# axiom_beta_plugin_module_1xHDMI_v0_4_e11.net
KiCad netlist of a schematic drawn in EAGLE
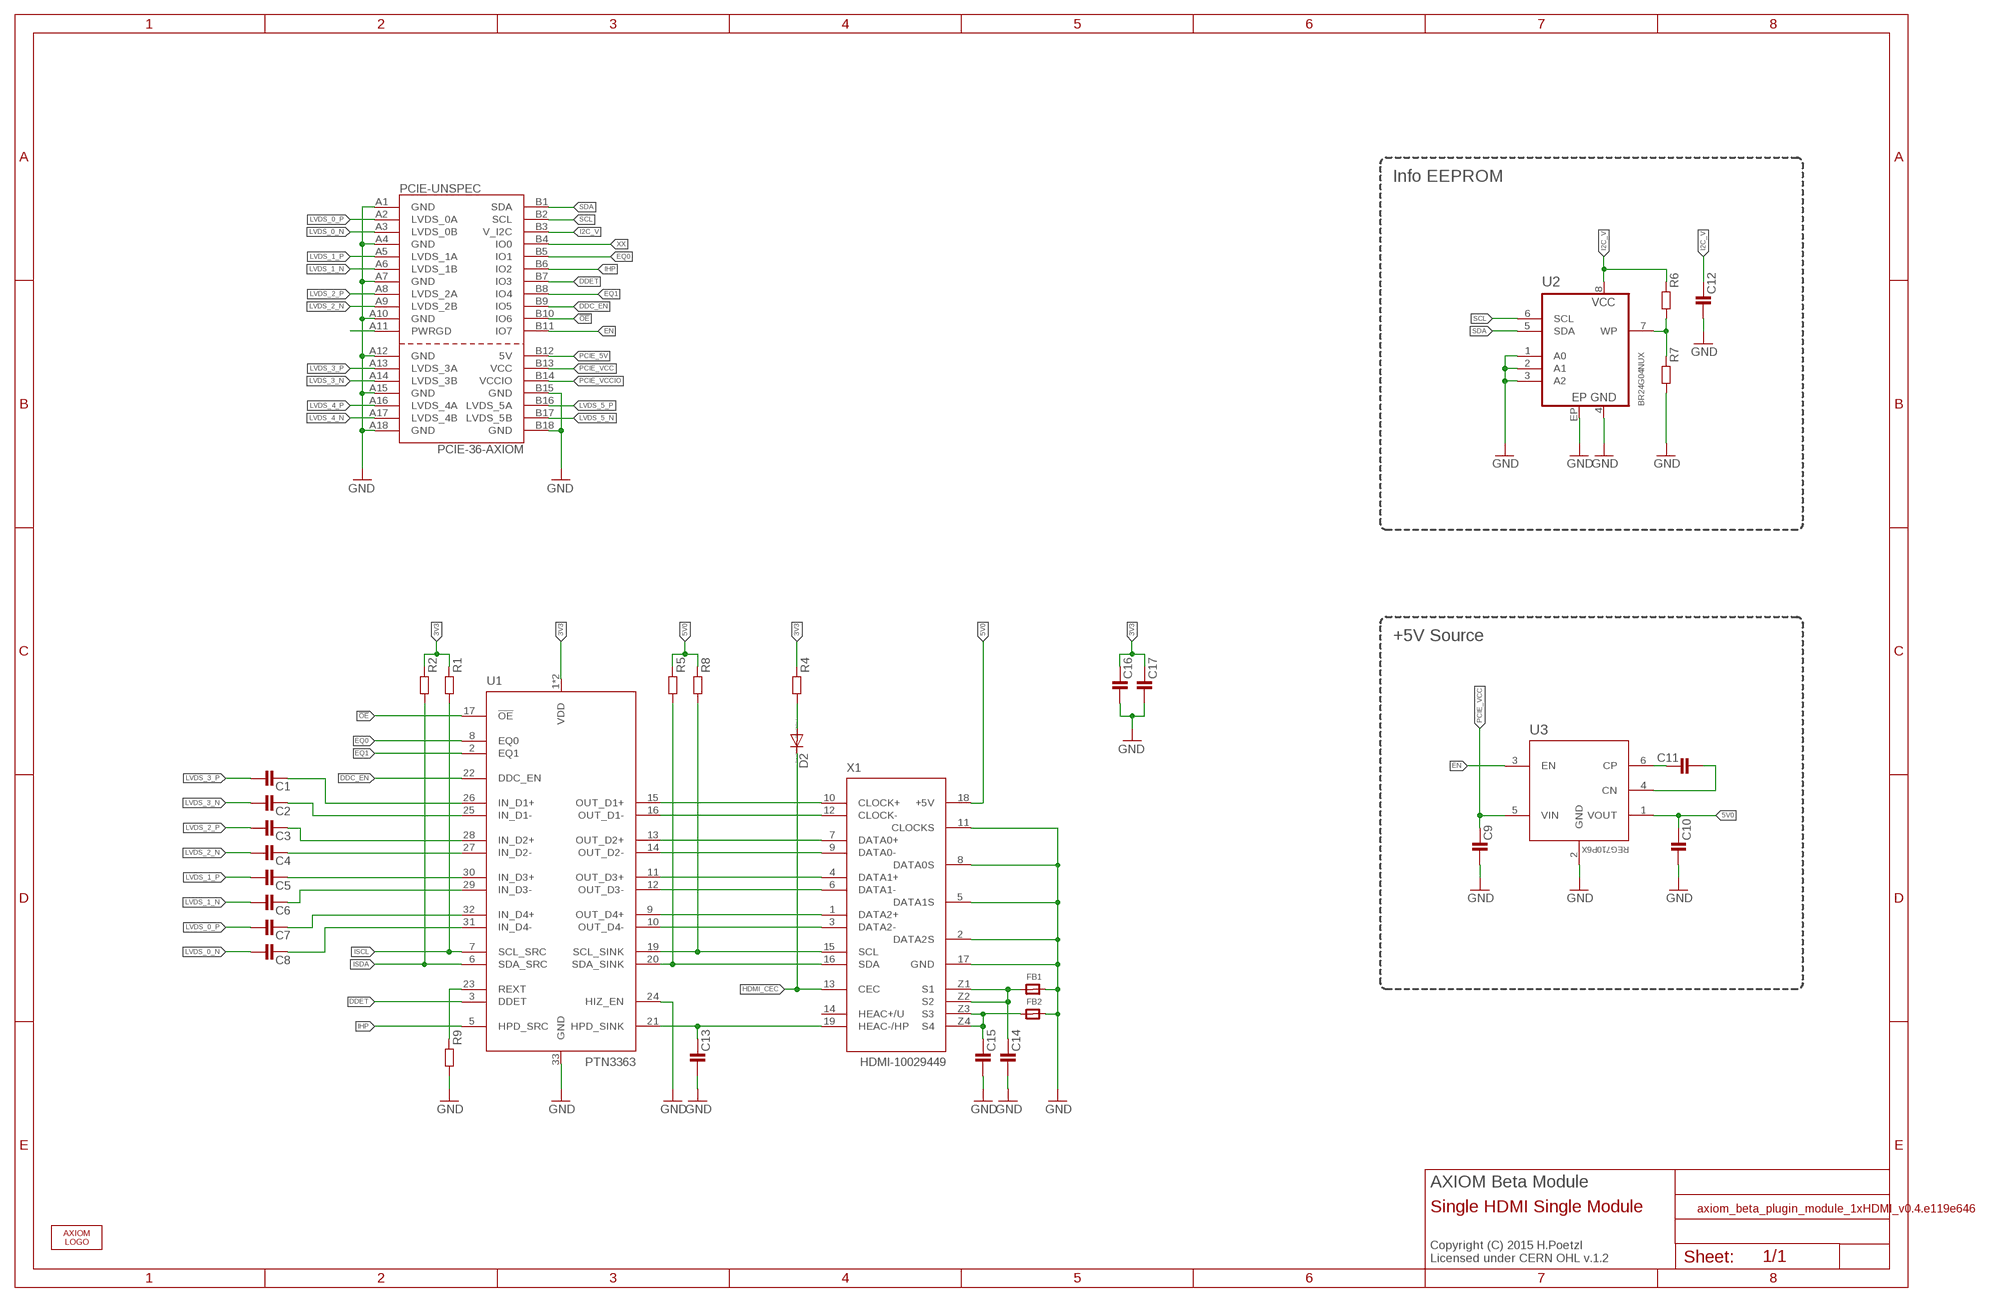
[diagram p0: schematic, sheet 1]

(export (version "E")
  (design (tool "Eeschema 10.0.6"))
  (components
    (comp (ref "C1")
      (value "C0402-B")
      (footprint "eagle-import:0402-B")
      (libsource (lib "eagle-import") (part "C0402-B"))
    )
    (comp (ref "C2")
      (value "C0402-B")
      (footprint "eagle-import:0402-B")
      (libsource (lib "eagle-import") (part "C0402-B"))
    )
    (comp (ref "C3")
      (value "C0402-B")
      (footprint "eagle-import:0402-B")
      (libsource (lib "eagle-import") (part "C0402-B"))
    )
    (comp (ref "C4")
      (value "C0402-B")
      (footprint "eagle-import:0402-B")
      (libsource (lib "eagle-import") (part "C0402-B"))
    )
    (comp (ref "C5")
      (value "C0402-B")
      (footprint "eagle-import:0402-B")
      (libsource (lib "eagle-import") (part "C0402-B"))
    )
    (comp (ref "C6")
      (value "C0402-B")
      (footprint "eagle-import:0402-B")
      (libsource (lib "eagle-import") (part "C0402-B"))
    )
    (comp (ref "C7")
      (value "C0402-B")
      (footprint "eagle-import:0402-B")
      (libsource (lib "eagle-import") (part "C0402-B"))
    )
    (comp (ref "C8")
      (value "C0402-B")
      (footprint "eagle-import:0402-B")
      (libsource (lib "eagle-import") (part "C0402-B"))
    )
    (comp (ref "C9")
      (value "C0603-B")
      (footprint "eagle-import:0603-B")
      (libsource (lib "eagle-import") (part "C0603-B"))
    )
    (comp (ref "C10")
      (value "C0603-B")
      (footprint "eagle-import:0603-B")
      (libsource (lib "eagle-import") (part "C0603-B"))
    )
    (comp (ref "C11")
      (value "C0603-B")
      (footprint "eagle-import:0603-B")
      (libsource (lib "eagle-import") (part "C0603-B"))
    )
    (comp (ref "C12")
      (value "C0402-B")
      (footprint "eagle-import:0402-B")
      (libsource (lib "eagle-import") (part "C0402-B"))
    )
    (comp (ref "C13")
      (value "C0402-B")
      (footprint "eagle-import:0402-B")
      (libsource (lib "eagle-import") (part "C0402-B"))
    )
    (comp (ref "C14")
      (value "C0402-B")
      (footprint "eagle-import:0402-B")
      (libsource (lib "eagle-import") (part "C0402-B"))
    )
    (comp (ref "C15")
      (value "C0402-B")
      (footprint "eagle-import:0402-B")
      (libsource (lib "eagle-import") (part "C0402-B"))
    )
    (comp (ref "C16")
      (value "C0402-B")
      (footprint "eagle-import:0402-B")
      (libsource (lib "eagle-import") (part "C0402-B"))
    )
    (comp (ref "C17")
      (value "C0402-B")
      (footprint "eagle-import:0402-B")
      (libsource (lib "eagle-import") (part "C0402-B"))
    )
    (comp (ref "D2")
      (value "DIODE-SOD523")
      (footprint "eagle-import:SOD523")
      (libsource (lib "eagle-import") (part "DIODE-SOD523"))
    )
    (comp (ref "FB1")
      (value "FERRITE_0603MP")
      (footprint "eagle-import:_0603MP")
      (libsource (lib "eagle-import") (part "FERRITE_0603MP"))
    )
    (comp (ref "FB2")
      (value "FERRITE_0603MP")
      (footprint "eagle-import:_0603MP")
      (libsource (lib "eagle-import") (part "FERRITE_0603MP"))
    )
    (comp (ref "PCIE-UNSPEC")
      (value "PCIE-36-AXIOM")
      (footprint "eagle-import:PCIE-36-AXIOM")
      (libsource (lib "eagle-import") (part "PCIE-36-AXIOM"))
    )
    (comp (ref "R1")
      (value "R0402-B")
      (footprint "eagle-import:0402-B")
      (libsource (lib "eagle-import") (part "R0402-B"))
    )
    (comp (ref "R2")
      (value "R0402-B")
      (footprint "eagle-import:0402-B")
      (libsource (lib "eagle-import") (part "R0402-B"))
    )
    (comp (ref "R4")
      (value "R0402-B")
      (footprint "eagle-import:0402-B")
      (libsource (lib "eagle-import") (part "R0402-B"))
    )
    (comp (ref "R5")
      (value "R0402-B")
      (footprint "eagle-import:0402-B")
      (libsource (lib "eagle-import") (part "R0402-B"))
    )
    (comp (ref "R6")
      (value "R0402-B")
      (footprint "eagle-import:0402-B")
      (libsource (lib "eagle-import") (part "R0402-B"))
    )
    (comp (ref "R7")
      (value "R0402-B")
      (footprint "eagle-import:0402-B")
      (libsource (lib "eagle-import") (part "R0402-B"))
    )
    (comp (ref "R8")
      (value "R0402-B")
      (footprint "eagle-import:0402-B")
      (libsource (lib "eagle-import") (part "R0402-B"))
    )
    (comp (ref "R9")
      (value "R0402-B")
      (footprint "eagle-import:0402-B")
      (libsource (lib "eagle-import") (part "R0402-B"))
    )
    (comp (ref "U$1")
      (value "AXIOM_LOGO459X70")
      (footprint "eagle-import:AXIOM_LOGO_459X70")
      (libsource (lib "eagle-import") (part "AXIOM_LOGO459X70"))
    )
    (comp (ref "U1")
      (value "PTN3363")
      (footprint "eagle-import:HVQFN32")
      (libsource (lib "eagle-import") (part "PTN3363"))
    )
    (comp (ref "U2")
      (value "BR24G04NUX")
      (footprint "eagle-import:DFN200X300X100-9N")
      (libsource (lib "eagle-import") (part "BR24G04NUX"))
    )
    (comp (ref "U3")
      (value "REG710P6X")
      (footprint "eagle-import:SOT65P210X110-6N")
      (libsource (lib "eagle-import") (part "REG710P6X"))
    )
    (comp (ref "X1")
      (value "HDMI-10029449")
      (footprint "eagle-import:10029449-X01XLF")
      (libsource (lib "eagle-import") (part "HDMI-10029449"))
    )
  )
  (nets
    (net (code "1") (name "/~{OE}") (class "Default")
      (node (ref "PCIE-UNSPEC") (pin "B10") (pinfunction "IO6_B10") (pintype "passive"))
      (node (ref "U1") (pin "17") (pinfunction "~{OE}_17") (pintype "bidirectional"))
    )
    (net (code "2") (name "3V3") (class "Default")
      (node (ref "C16") (pin "1") (pinfunction "1_1") (pintype "passive"))
      (node (ref "C17") (pin "1") (pinfunction "1_1") (pintype "passive"))
      (node (ref "R1") (pin "1") (pinfunction "1_1") (pintype "passive"))
      (node (ref "R2") (pin "1") (pinfunction "1_1") (pintype "passive"))
      (node (ref "R4") (pin "1") (pinfunction "1_1") (pintype "passive"))
      (node (ref "U1") (pin "1") (pinfunction "VDD_1") (pintype "power_in"))
      (node (ref "U1") (pin "18") (pinfunction "VDD_18") (pintype "power_in"))
    )
    (net (code "3") (name "5V0") (class "Default")
      (node (ref "C10") (pin "1") (pinfunction "1_1") (pintype "passive"))
      (node (ref "R5") (pin "1") (pinfunction "1_1") (pintype "passive"))
      (node (ref "R8") (pin "1") (pinfunction "1_1") (pintype "passive"))
      (node (ref "U3") (pin "1") (pinfunction "VOUT_1") (pintype "output"))
      (node (ref "X1") (pin "18") (pinfunction "+5V_18") (pintype "power_in"))
    )
    (net (code "4") (name "DDC_EN") (class "Default")
      (node (ref "PCIE-UNSPEC") (pin "B9") (pinfunction "IO5_B9") (pintype "passive"))
      (node (ref "U1") (pin "22") (pinfunction "DDC_EN_22") (pintype "bidirectional"))
    )
    (net (code "5") (name "DDET") (class "Default")
      (node (ref "PCIE-UNSPEC") (pin "B7") (pinfunction "IO3_B7") (pintype "passive"))
      (node (ref "U1") (pin "3") (pinfunction "DDET_3") (pintype "bidirectional"))
    )
    (net (code "6") (name "EN") (class "Default")
      (node (ref "PCIE-UNSPEC") (pin "B11") (pinfunction "IO7_B11") (pintype "passive"))
      (node (ref "U3") (pin "3") (pinfunction "EN_3") (pintype "input"))
    )
    (net (code "7") (name "EQ0") (class "Default")
      (node (ref "PCIE-UNSPEC") (pin "B5") (pinfunction "IO1_B5") (pintype "passive"))
      (node (ref "U1") (pin "8") (pinfunction "EQ0_8") (pintype "bidirectional"))
    )
    (net (code "8") (name "EQ1") (class "Default")
      (node (ref "PCIE-UNSPEC") (pin "B8") (pinfunction "IO4_B8") (pintype "passive"))
      (node (ref "U1") (pin "2") (pinfunction "EQ1_2") (pintype "bidirectional"))
    )
    (net (code "9") (name "GND") (class "Default")
      (node (ref "C10") (pin "2") (pinfunction "2_2") (pintype "passive"))
      (node (ref "C12") (pin "2") (pinfunction "2_2") (pintype "passive"))
      (node (ref "C13") (pin "2") (pinfunction "2_2") (pintype "passive"))
      (node (ref "C14") (pin "2") (pinfunction "2_2") (pintype "passive"))
      (node (ref "C15") (pin "2") (pinfunction "2_2") (pintype "passive"))
      (node (ref "C16") (pin "2") (pinfunction "2_2") (pintype "passive"))
      (node (ref "C17") (pin "2") (pinfunction "2_2") (pintype "passive"))
      (node (ref "C9") (pin "2") (pinfunction "2_2") (pintype "passive"))
      (node (ref "FB1") (pin "2") (pinfunction "P$2_2") (pintype "passive"))
      (node (ref "FB2") (pin "2") (pinfunction "P$2_2") (pintype "passive"))
      (node (ref "PCIE-UNSPEC") (pin "A1") (pinfunction "GND_A1") (pintype "passive"))
      (node (ref "PCIE-UNSPEC") (pin "A10") (pinfunction "GND_A10") (pintype "passive"))
      (node (ref "PCIE-UNSPEC") (pin "A12") (pinfunction "GND_A12") (pintype "passive"))
      (node (ref "PCIE-UNSPEC") (pin "A15") (pinfunction "GND_A15") (pintype "passive"))
      (node (ref "PCIE-UNSPEC") (pin "A18") (pinfunction "GND_A18") (pintype "passive"))
      (node (ref "PCIE-UNSPEC") (pin "A4") (pinfunction "GND_A4") (pintype "passive"))
      (node (ref "PCIE-UNSPEC") (pin "A7") (pinfunction "GND_A7") (pintype "passive"))
      (node (ref "PCIE-UNSPEC") (pin "B15") (pinfunction "GND_B15") (pintype "passive"))
      (node (ref "PCIE-UNSPEC") (pin "B18") (pinfunction "GND_B18") (pintype "passive"))
      (node (ref "R7") (pin "2") (pinfunction "2_2") (pintype "passive"))
      (node (ref "R9") (pin "2") (pinfunction "2_2") (pintype "passive"))
      (node (ref "U1") (pin "24") (pinfunction "HIZ_EN_24") (pintype "bidirectional"))
      (node (ref "U1") (pin "33") (pinfunction "GND_33") (pintype "bidirectional"))
      (node (ref "U2") (pin "1") (pinfunction "A0_1") (pintype "input"))
      (node (ref "U2") (pin "2") (pinfunction "A1_2") (pintype "input"))
      (node (ref "U2") (pin "3") (pinfunction "A2_3") (pintype "input"))
      (node (ref "U2") (pin "4") (pinfunction "GND_4") (pintype "passive"))
      (node (ref "U2") (pin "EP") (pinfunction "EP_EP") (pintype "passive"))
      (node (ref "U3") (pin "2") (pinfunction "GND_2") (pintype "passive"))
      (node (ref "X1") (pin "11") (pinfunction "CLOCKS_11") (pintype "power_in"))
      (node (ref "X1") (pin "17") (pinfunction "GND_17") (pintype "bidirectional"))
      (node (ref "X1") (pin "2") (pinfunction "DATA2S_2") (pintype "power_in"))
      (node (ref "X1") (pin "5") (pinfunction "DATA1S_5") (pintype "power_in"))
      (node (ref "X1") (pin "8") (pinfunction "DATA0S_8") (pintype "power_in"))
    )
    (net (code "10") (name "HDMI_CEC") (class "Default")
      (node (ref "D2") (pin "C") (pinfunction "C_C") (pintype "passive"))
      (node (ref "X1") (pin "13") (pinfunction "CEC_13") (pintype "bidirectional"))
    )
    (net (code "11") (name "I2C_V") (class "Default")
      (node (ref "C12") (pin "1") (pinfunction "1_1") (pintype "passive"))
      (node (ref "PCIE-UNSPEC") (pin "B3") (pinfunction "V_I2C_B3") (pintype "passive"))
      (node (ref "R6") (pin "1") (pinfunction "1_1") (pintype "passive"))
      (node (ref "U2") (pin "8") (pinfunction "VCC_8") (pintype "power_in"))
    )
    (net (code "12") (name "IHP") (class "Default")
      (node (ref "PCIE-UNSPEC") (pin "B6") (pinfunction "IO2_B6") (pintype "passive"))
      (node (ref "U1") (pin "5") (pinfunction "HPD_SRC_5") (pintype "bidirectional"))
    )
    (net (code "13") (name "ISCL") (class "Default")
      (node (ref "R1") (pin "2") (pinfunction "2_2") (pintype "passive"))
      (node (ref "U1") (pin "7") (pinfunction "SCL_SRC_7") (pintype "bidirectional"))
    )
    (net (code "14") (name "ISDA") (class "Default")
      (node (ref "R2") (pin "2") (pinfunction "2_2") (pintype "passive"))
      (node (ref "U1") (pin "6") (pinfunction "SDA_SRC_6") (pintype "bidirectional"))
    )
    (net (code "15") (name "LVDS_0_N") (class "Default")
      (node (ref "C8") (pin "2") (pinfunction "2_2") (pintype "passive"))
      (node (ref "PCIE-UNSPEC") (pin "A3") (pinfunction "LVDS_0B_A3") (pintype "passive"))
    )
    (net (code "16") (name "LVDS_0_P") (class "Default")
      (node (ref "C7") (pin "2") (pinfunction "2_2") (pintype "passive"))
      (node (ref "PCIE-UNSPEC") (pin "A2") (pinfunction "LVDS_0A_A2") (pintype "passive"))
    )
    (net (code "17") (name "LVDS_1_N") (class "Default")
      (node (ref "C6") (pin "2") (pinfunction "2_2") (pintype "passive"))
      (node (ref "PCIE-UNSPEC") (pin "A6") (pinfunction "LVDS_1B_A6") (pintype "passive"))
    )
    (net (code "18") (name "LVDS_1_P") (class "Default")
      (node (ref "C5") (pin "2") (pinfunction "2_2") (pintype "passive"))
      (node (ref "PCIE-UNSPEC") (pin "A5") (pinfunction "LVDS_1A_A5") (pintype "passive"))
    )
    (net (code "19") (name "LVDS_2_N") (class "Default")
      (node (ref "C4") (pin "2") (pinfunction "2_2") (pintype "passive"))
      (node (ref "PCIE-UNSPEC") (pin "A9") (pinfunction "LVDS_2B_A9") (pintype "passive"))
    )
    (net (code "20") (name "LVDS_2_P") (class "Default")
      (node (ref "C3") (pin "2") (pinfunction "2_2") (pintype "passive"))
      (node (ref "PCIE-UNSPEC") (pin "A8") (pinfunction "LVDS_2A_A8") (pintype "passive"))
    )
    (net (code "21") (name "LVDS_3_N") (class "Default")
      (node (ref "C2") (pin "2") (pinfunction "2_2") (pintype "passive"))
      (node (ref "PCIE-UNSPEC") (pin "A14") (pinfunction "LVDS_3B_A14") (pintype "passive"))
    )
    (net (code "22") (name "LVDS_3_P") (class "Default")
      (node (ref "C1") (pin "2") (pinfunction "2_2") (pintype "passive"))
      (node (ref "PCIE-UNSPEC") (pin "A13") (pinfunction "LVDS_3A_A13") (pintype "passive"))
    )
    (net (code "23") (name "LVDS_4_N") (class "Default")
      (node (ref "PCIE-UNSPEC") (pin "A17") (pinfunction "LVDS_4B_A17") (pintype "passive"))
    )
    (net (code "24") (name "LVDS_4_P") (class "Default")
      (node (ref "PCIE-UNSPEC") (pin "A16") (pinfunction "LVDS_4A_A16") (pintype "passive"))
    )
    (net (code "25") (name "LVDS_5_N") (class "Default")
      (node (ref "PCIE-UNSPEC") (pin "B17") (pinfunction "LVDS_5B_B17") (pintype "passive"))
    )
    (net (code "26") (name "LVDS_5_P") (class "Default")
      (node (ref "PCIE-UNSPEC") (pin "B16") (pinfunction "LVDS_5A_B16") (pintype "passive"))
    )
    (net (code "27") (name "Net-(D2-PadA)") (class "Default")
      (node (ref "D2") (pin "A") (pinfunction "A_A") (pintype "passive"))
      (node (ref "R4") (pin "2") (pinfunction "2_2") (pintype "passive"))
    )
    (net (code "28") (name "Net-(FB1-P$1)") (class "Default")
      (node (ref "C14") (pin "1") (pinfunction "1_1") (pintype "passive"))
      (node (ref "FB1") (pin "1") (pinfunction "P$1_1") (pintype "passive"))
      (node (ref "X1") (pin "Z1") (pinfunction "S1_Z1") (pintype "power_in"))
      (node (ref "X1") (pin "Z2") (pinfunction "S2_Z2") (pintype "power_in"))
    )
    (net (code "29") (name "Net-(FB2-P$1)") (class "Default")
      (node (ref "C15") (pin "1") (pinfunction "1_1") (pintype "passive"))
      (node (ref "FB2") (pin "1") (pinfunction "P$1_1") (pintype "passive"))
      (node (ref "X1") (pin "Z3") (pinfunction "S3_Z3") (pintype "power_in"))
      (node (ref "X1") (pin "Z4") (pinfunction "S4_Z4") (pintype "power_in"))
    )
    (net (code "30") (name "Net-(U1-HPD_SINK)") (class "Default")
      (node (ref "C13") (pin "1") (pinfunction "1_1") (pintype "passive"))
      (node (ref "U1") (pin "21") (pinfunction "HPD_SINK_21") (pintype "bidirectional"))
      (node (ref "X1") (pin "19") (pinfunction "HEAC-/HP_19") (pintype "bidirectional"))
    )
    (net (code "31") (name "Net-(U1-IN_D1+)") (class "Default")
      (node (ref "C1") (pin "1") (pinfunction "1_1") (pintype "passive"))
      (node (ref "U1") (pin "26") (pinfunction "IN_D1+_26") (pintype "bidirectional"))
    )
    (net (code "32") (name "Net-(U1-IN_D1-)") (class "Default")
      (node (ref "C2") (pin "1") (pinfunction "1_1") (pintype "passive"))
      (node (ref "U1") (pin "25") (pinfunction "IN_D1-_25") (pintype "bidirectional"))
    )
    (net (code "33") (name "Net-(U1-IN_D2+)") (class "Default")
      (node (ref "C3") (pin "1") (pinfunction "1_1") (pintype "passive"))
      (node (ref "U1") (pin "28") (pinfunction "IN_D2+_28") (pintype "bidirectional"))
    )
    (net (code "34") (name "Net-(U1-IN_D2-)") (class "Default")
      (node (ref "C4") (pin "1") (pinfunction "1_1") (pintype "passive"))
      (node (ref "U1") (pin "27") (pinfunction "IN_D2-_27") (pintype "bidirectional"))
    )
    (net (code "35") (name "Net-(U1-IN_D3+)") (class "Default")
      (node (ref "C5") (pin "1") (pinfunction "1_1") (pintype "passive"))
      (node (ref "U1") (pin "30") (pinfunction "IN_D3+_30") (pintype "bidirectional"))
    )
    (net (code "36") (name "Net-(U1-IN_D3-)") (class "Default")
      (node (ref "C6") (pin "1") (pinfunction "1_1") (pintype "passive"))
      (node (ref "U1") (pin "29") (pinfunction "IN_D3-_29") (pintype "bidirectional"))
    )
    (net (code "37") (name "Net-(U1-IN_D4+)") (class "Default")
      (node (ref "C7") (pin "1") (pinfunction "1_1") (pintype "passive"))
      (node (ref "U1") (pin "32") (pinfunction "IN_D4+_32") (pintype "bidirectional"))
    )
    (net (code "38") (name "Net-(U1-IN_D4-)") (class "Default")
      (node (ref "C8") (pin "1") (pinfunction "1_1") (pintype "passive"))
      (node (ref "U1") (pin "31") (pinfunction "IN_D4-_31") (pintype "bidirectional"))
    )
    (net (code "39") (name "Net-(U1-OUT_D1+)") (class "Default")
      (node (ref "U1") (pin "15") (pinfunction "OUT_D1+_15") (pintype "bidirectional"))
      (node (ref "X1") (pin "10") (pinfunction "CLOCK+_10") (pintype "bidirectional"))
    )
    (net (code "40") (name "Net-(U1-OUT_D1-)") (class "Default")
      (node (ref "U1") (pin "16") (pinfunction "OUT_D1-_16") (pintype "bidirectional"))
      (node (ref "X1") (pin "12") (pinfunction "CLOCK-_12") (pintype "bidirectional"))
    )
    (net (code "41") (name "Net-(U1-OUT_D2+)") (class "Default")
      (node (ref "U1") (pin "13") (pinfunction "OUT_D2+_13") (pintype "bidirectional"))
      (node (ref "X1") (pin "7") (pinfunction "DATA0+_7") (pintype "bidirectional"))
    )
    (net (code "42") (name "Net-(U1-OUT_D2-)") (class "Default")
      (node (ref "U1") (pin "14") (pinfunction "OUT_D2-_14") (pintype "bidirectional"))
      (node (ref "X1") (pin "9") (pinfunction "DATA0-_9") (pintype "bidirectional"))
    )
    (net (code "43") (name "Net-(U1-OUT_D3+)") (class "Default")
      (node (ref "U1") (pin "11") (pinfunction "OUT_D3+_11") (pintype "bidirectional"))
      (node (ref "X1") (pin "4") (pinfunction "DATA1+_4") (pintype "bidirectional"))
    )
    (net (code "44") (name "Net-(U1-OUT_D3-)") (class "Default")
      (node (ref "U1") (pin "12") (pinfunction "OUT_D3-_12") (pintype "bidirectional"))
      (node (ref "X1") (pin "6") (pinfunction "DATA1-_6") (pintype "bidirectional"))
    )
    (net (code "45") (name "Net-(U1-OUT_D4+)") (class "Default")
      (node (ref "U1") (pin "9") (pinfunction "OUT_D4+_9") (pintype "bidirectional"))
      (node (ref "X1") (pin "1") (pinfunction "DATA2+_1") (pintype "bidirectional"))
    )
    (net (code "46") (name "Net-(U1-OUT_D4-)") (class "Default")
      (node (ref "U1") (pin "10") (pinfunction "OUT_D4-_10") (pintype "bidirectional"))
      (node (ref "X1") (pin "3") (pinfunction "DATA2-_3") (pintype "bidirectional"))
    )
    (net (code "47") (name "Net-(U1-REXT)") (class "Default")
      (node (ref "R9") (pin "1") (pinfunction "1_1") (pintype "passive"))
      (node (ref "U1") (pin "23") (pinfunction "REXT_23") (pintype "bidirectional"))
    )
    (net (code "48") (name "Net-(U1-SCL_SINK)") (class "Default")
      (node (ref "R8") (pin "2") (pinfunction "2_2") (pintype "passive"))
      (node (ref "U1") (pin "19") (pinfunction "SCL_SINK_19") (pintype "bidirectional"))
      (node (ref "X1") (pin "15") (pinfunction "SCL_15") (pintype "bidirectional"))
    )
    (net (code "49") (name "Net-(U1-SDA_SINK)") (class "Default")
      (node (ref "R5") (pin "2") (pinfunction "2_2") (pintype "passive"))
      (node (ref "U1") (pin "20") (pinfunction "SDA_SINK_20") (pintype "bidirectional"))
      (node (ref "X1") (pin "16") (pinfunction "SDA_16") (pintype "bidirectional"))
    )
    (net (code "50") (name "Net-(U2-WP)") (class "Default")
      (node (ref "R6") (pin "2") (pinfunction "2_2") (pintype "passive"))
      (node (ref "R7") (pin "1") (pinfunction "1_1") (pintype "passive"))
      (node (ref "U2") (pin "7") (pinfunction "WP_7") (pintype "input"))
    )
    (net (code "51") (name "Net-(U3-CN)") (class "Default")
      (node (ref "C11") (pin "2") (pinfunction "2_2") (pintype "passive"))
      (node (ref "U3") (pin "4") (pinfunction "CN_4") (pintype "power_in"))
    )
    (net (code "52") (name "Net-(U3-CP)") (class "Default")
      (node (ref "C11") (pin "1") (pinfunction "1_1") (pintype "passive"))
      (node (ref "U3") (pin "6") (pinfunction "CP_6") (pintype "output"))
    )
    (net (code "53") (name "PCIE_5V") (class "Default")
      (node (ref "PCIE-UNSPEC") (pin "B12") (pinfunction "5V_B12") (pintype "passive"))
    )
    (net (code "54") (name "PCIE_VCC") (class "Default")
      (node (ref "C9") (pin "1") (pinfunction "1_1") (pintype "passive"))
      (node (ref "PCIE-UNSPEC") (pin "B13") (pinfunction "VCC_B13") (pintype "passive"))
      (node (ref "U3") (pin "5") (pinfunction "VIN_5") (pintype "power_in"))
    )
    (net (code "55") (name "PCIE_VCCIO") (class "Default")
      (node (ref "PCIE-UNSPEC") (pin "B14") (pinfunction "VCCIO_B14") (pintype "passive"))
    )
    (net (code "56") (name "SCL") (class "Default")
      (node (ref "PCIE-UNSPEC") (pin "B2") (pinfunction "SCL_B2") (pintype "passive"))
      (node (ref "U2") (pin "6") (pinfunction "SCL_6") (pintype "input"))
    )
    (net (code "57") (name "SDA") (class "Default")
      (node (ref "PCIE-UNSPEC") (pin "B1") (pinfunction "SDA_B1") (pintype "passive"))
      (node (ref "U2") (pin "5") (pinfunction "SDA_5") (pintype "bidirectional"))
    )
    (net (code "58") (name "XX") (class "Default")
      (node (ref "PCIE-UNSPEC") (pin "B4") (pinfunction "IO0_B4") (pintype "passive"))
    )
    (net (code "59") (name "unconnected-(PCIE-UNSPEC-PWRGD-PadA11)") (class "Default")
      (node (ref "PCIE-UNSPEC") (pin "A11") (pinfunction "PWRGD_A11") (pintype "passive"))
    )
    (net (code "60") (name "unconnected-(X1-HEAC+{slash}U-Pad14)") (class "Default")
      (node (ref "X1") (pin "14") (pinfunction "HEAC+/U_14") (pintype "bidirectional"))
    )
  )
)
